# SolBout.net
KiCad netlist of a schematic drawn in Altium Designer
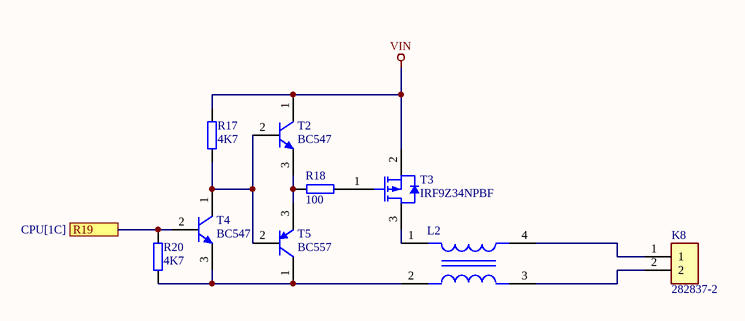
[diagram p0: SolBout.SchDoc]

(export (version "E")
  (design (tool "Eeschema 10.0.6"))
  (components
    (comp (ref "K8")
      (value "282837-2")
      (footprint "TE_282837-2")
      (fields (field (name "MF") "TE Connectivity"))
      (libsource (lib "282837-2") (part "282837-2"))
    )
    (comp (ref "L2")
      (value "~")
      (footprint "2545")
      (libsource (lib "Soldeerstation_Final") (part "Common_Mode_Choke"))
    )
    (comp (ref "R17")
      (value "4K7")
      (footprint "CC_0805_m")
      (fields (field (name "MANUFACTURER") "Vishay Dale") (field (name "PART NUMBER") "CRCW08050000Z0EA"))
      (libsource (lib "Soldeerstation_Final") (part "Resistor"))
    )
    (comp (ref "R18")
      (value "100")
      (footprint "CC_0805_m")
      (fields (field (name "MANUFACTURER") "Vishay Dale") (field (name "PART NUMBER") "CRCW08050000Z0EA"))
      (libsource (lib "Soldeerstation_Final") (part "Resistor"))
    )
    (comp (ref "R20")
      (value "4K7")
      (footprint "CC_0805_m")
      (fields (field (name "MANUFACTURER") "Vishay Dale") (field (name "PART NUMBER") "CRCW08050000Z0EA"))
      (libsource (lib "Soldeerstation_Final") (part "Resistor"))
    )
    (comp (ref "T2")
      (value "BC547")
      (footprint "SOT_23")
      (fields (field (name "MANUFACTURER") "On Semiconductor") (field (name "PARTNUMBER") "BC547C"))
      (libsource (lib "Soldeerstation_Final") (part "Transistor_NPN"))
    )
    (comp (ref "T3")
      (value "IRF9Z34NPBF")
      (footprint "TO_252")
      (fields (field (name "MANUFACTURER") "Fairchild Semiconductor"))
      (libsource (lib "Soldeerstation_Final") (part "MOSFET_P"))
    )
    (comp (ref "T4")
      (value "BC547")
      (footprint "SOT_23")
      (fields (field (name "MANUFACTURER") "On Semiconductor") (field (name "PARTNUMBER") "BC547C"))
      (libsource (lib "Soldeerstation_Final") (part "Transistor_NPN"))
    )
    (comp (ref "T5")
      (value "BC557")
      (footprint "SOT_23")
      (fields (field (name "MANUFACTURER") "On Semiconductor") (field (name "PARTNUMBER") "BC557C"))
      (libsource (lib "Soldeerstation_Final") (part "Transistor_PNP"))
    )
  )
  (nets
    (net (code "1") (name "/R19") (class "Default")
      (node (ref "R20") (pin "2") (pinfunction "2_2") (pintype "passive"))
      (node (ref "T4") (pin "2") (pinfunction "B_2") (pintype "passive"))
    )
    (net (code "2") (name "Net-(K8-Pad1)") (class "Default")
      (node (ref "K8") (pin "1") (pinfunction "1_1") (pintype "passive"))
      (node (ref "L2") (pin "4") (pinfunction "4_4") (pintype "passive"))
    )
    (net (code "3") (name "Net-(K8-Pad2)") (class "Default")
      (node (ref "K8") (pin "2") (pinfunction "2_2") (pintype "passive"))
      (node (ref "L2") (pin "3") (pinfunction "3_3") (pintype "passive"))
    )
    (net (code "4") (name "Net-(T2-B)") (class "Default")
      (node (ref "R17") (pin "1") (pinfunction "1_1") (pintype "passive"))
      (node (ref "T2") (pin "2") (pinfunction "B_2") (pintype "passive"))
      (node (ref "T4") (pin "1") (pinfunction "C_1") (pintype "passive"))
      (node (ref "T5") (pin "2") (pinfunction "B_2") (pintype "passive"))
    )
    (net (code "5") (name "Net-(T2-E)") (class "Default")
      (node (ref "R18") (pin "1") (pinfunction "1_1") (pintype "passive"))
      (node (ref "T2") (pin "3") (pinfunction "E_3") (pintype "passive"))
      (node (ref "T5") (pin "3") (pinfunction "E_3") (pintype "passive"))
    )
    (net (code "6") (name "Net-(T3-DRAIN)") (class "Default")
      (node (ref "L2") (pin "1") (pinfunction "1_1") (pintype "passive"))
      (node (ref "T3") (pin "3") (pinfunction "DRAIN_3") (pintype "passive"))
    )
    (net (code "7") (name "Net-(T3-GATE)") (class "Default")
      (node (ref "R18") (pin "2") (pinfunction "2_2") (pintype "passive"))
      (node (ref "T3") (pin "1") (pinfunction "GATE_1") (pintype "passive"))
    )
    (net (code "8") (name "Net-(T4-E)") (class "Default")
      (node (ref "L2") (pin "2") (pinfunction "2_2") (pintype "passive"))
      (node (ref "R20") (pin "1") (pinfunction "1_1") (pintype "passive"))
      (node (ref "T4") (pin "3") (pinfunction "E_3") (pintype "passive"))
      (node (ref "T5") (pin "1") (pinfunction "C_1") (pintype "passive"))
    )
    (net (code "9") (name "VIN") (class "Default")
      (node (ref "R17") (pin "2") (pinfunction "2_2") (pintype "passive"))
      (node (ref "T2") (pin "1") (pinfunction "C_1") (pintype "passive"))
      (node (ref "T3") (pin "2") (pinfunction "SOURCE_2") (pintype "passive"))
    )
  )
)
